# SMD_RGB_COM_BC639_REV5.net
KiCad netlist of a schematic drawn in EAGLE
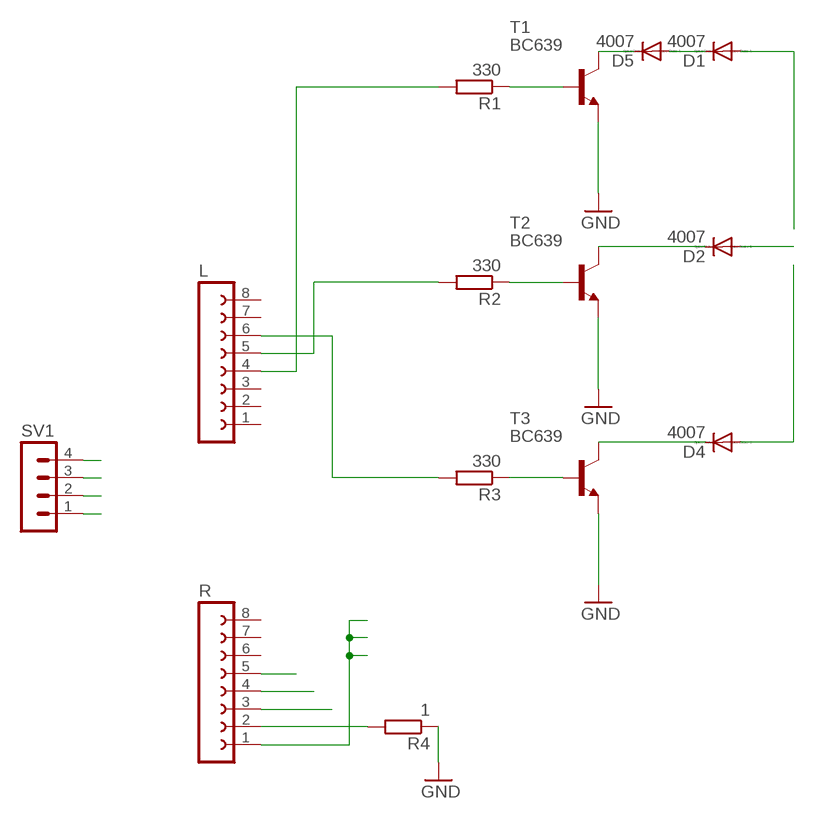
[diagram p0: schematic, sheet 1]

(export (version "E")
  (design (tool "Eeschema 10.0.6"))
  (components
    (comp (ref "D1")
      (value "4007")
      (footprint "eagle-import:DO35-7")
      (libsource (lib "eagle-import") (part "1N4148DO35-7"))
    )
    (comp (ref "D2")
      (value "4007")
      (footprint "eagle-import:DO35-7")
      (libsource (lib "eagle-import") (part "1N4148DO35-7"))
    )
    (comp (ref "D4")
      (value "4007")
      (footprint "eagle-import:DO35-7")
      (libsource (lib "eagle-import") (part "1N4148DO35-7"))
    )
    (comp (ref "D5")
      (value "4007")
      (footprint "eagle-import:DO35-7")
      (libsource (lib "eagle-import") (part "1N4148DO35-7"))
    )
    (comp (ref "L")
      (value "FE08-1")
      (footprint "eagle-import:FE08")
      (libsource (lib "eagle-import") (part "FE08-1"))
    )
    (comp (ref "R")
      (value "FE08-1")
      (footprint "eagle-import:FE08")
      (libsource (lib "eagle-import") (part "FE08-1"))
    )
    (comp (ref "R1")
      (value "330")
      (footprint "eagle-import:0204_7")
      (libsource (lib "eagle-import") (part "R-EU_0204/7"))
    )
    (comp (ref "R2")
      (value "330")
      (footprint "eagle-import:0204_7")
      (libsource (lib "eagle-import") (part "R-EU_0204/7"))
    )
    (comp (ref "R3")
      (value "330")
      (footprint "eagle-import:0204_7")
      (libsource (lib "eagle-import") (part "R-EU_0204/7"))
    )
    (comp (ref "R4")
      (value "1")
      (footprint "eagle-import:0204_7")
      (libsource (lib "eagle-import") (part "R-EU_0204/7"))
    )
    (comp (ref "SV1")
      (value "MA04-1")
      (footprint "eagle-import:MA04-1")
      (libsource (lib "eagle-import") (part "MA04-1"))
    )
    (comp (ref "T1")
      (value "BC639")
      (footprint "eagle-import:TO92-ECB")
      (libsource (lib "eagle-import") (part "-NPN-TO92-ECBBC639"))
    )
    (comp (ref "T2")
      (value "BC639")
      (footprint "eagle-import:TO92-ECB")
      (libsource (lib "eagle-import") (part "-NPN-TO92-ECBBC639"))
    )
    (comp (ref "T3")
      (value "BC639")
      (footprint "eagle-import:TO92-ECB")
      (libsource (lib "eagle-import") (part "-NPN-TO92-ECBBC639"))
    )
  )
  (nets
    (net (code "1") (name "/+5V") (class "Default")
      (node (ref "R") (pin "1") (pinfunction "1_1") (pintype "passive"))
      (node (ref "SV1") (pin "4") (pinfunction "4_4") (pintype "passive"))
    )
    (net (code "2") (name "/BO") (class "Default")
      (node (ref "D4") (pin "A") (pinfunction "A_A") (pintype "passive"))
      (node (ref "SV1") (pin "3") (pinfunction "3_3") (pintype "passive"))
    )
    (net (code "3") (name "/GO") (class "Default")
      (node (ref "D2") (pin "A") (pinfunction "A_A") (pintype "passive"))
      (node (ref "SV1") (pin "2") (pinfunction "2_2") (pintype "passive"))
    )
    (net (code "4") (name "/RO") (class "Default")
      (node (ref "D1") (pin "A") (pinfunction "A_A") (pintype "passive"))
      (node (ref "SV1") (pin "1") (pinfunction "1_1") (pintype "passive"))
    )
    (net (code "5") (name "GND") (class "Default")
      (node (ref "R4") (pin "1") (pinfunction "1_1") (pintype "passive"))
      (node (ref "T1") (pin "E") (pinfunction "E_E") (pintype "passive"))
      (node (ref "T2") (pin "E") (pinfunction "E_E") (pintype "passive"))
      (node (ref "T3") (pin "E") (pinfunction "E_E") (pintype "passive"))
    )
    (net (code "6") (name "Net-(D1-PadC)") (class "Default")
      (node (ref "D1") (pin "C") (pinfunction "C_C") (pintype "passive"))
      (node (ref "D5") (pin "A") (pinfunction "A_A") (pintype "passive"))
    )
    (net (code "7") (name "Net-(D2-PadC)") (class "Default")
      (node (ref "D2") (pin "C") (pinfunction "C_C") (pintype "passive"))
      (node (ref "T2") (pin "C") (pinfunction "C_C") (pintype "passive"))
    )
    (net (code "8") (name "Net-(D4-PadC)") (class "Default")
      (node (ref "D4") (pin "C") (pinfunction "C_C") (pintype "passive"))
      (node (ref "T3") (pin "C") (pinfunction "C_C") (pintype "passive"))
    )
    (net (code "9") (name "Net-(D5-PadC)") (class "Default")
      (node (ref "D5") (pin "C") (pinfunction "C_C") (pintype "passive"))
      (node (ref "T1") (pin "C") (pinfunction "C_C") (pintype "passive"))
    )
    (net (code "10") (name "Net-(L-Pad4)") (class "Default")
      (node (ref "L") (pin "4") (pinfunction "4_4") (pintype "passive"))
      (node (ref "R1") (pin "2") (pinfunction "2_2") (pintype "passive"))
    )
    (net (code "11") (name "Net-(L-Pad5)") (class "Default")
      (node (ref "L") (pin "5") (pinfunction "5_5") (pintype "passive"))
      (node (ref "R2") (pin "2") (pinfunction "2_2") (pintype "passive"))
    )
    (net (code "12") (name "Net-(L-Pad6)") (class "Default")
      (node (ref "L") (pin "6") (pinfunction "6_6") (pintype "passive"))
      (node (ref "R3") (pin "2") (pinfunction "2_2") (pintype "passive"))
    )
    (net (code "13") (name "Net-(R-Pad2)") (class "Default")
      (node (ref "R") (pin "2") (pinfunction "2_2") (pintype "passive"))
      (node (ref "R4") (pin "2") (pinfunction "2_2") (pintype "passive"))
    )
    (net (code "14") (name "Net-(R1-Pad1)") (class "Default")
      (node (ref "R1") (pin "1") (pinfunction "1_1") (pintype "passive"))
      (node (ref "T1") (pin "B") (pinfunction "B_B") (pintype "passive"))
    )
    (net (code "15") (name "Net-(R2-Pad1)") (class "Default")
      (node (ref "R2") (pin "1") (pinfunction "1_1") (pintype "passive"))
      (node (ref "T2") (pin "B") (pinfunction "B_B") (pintype "passive"))
    )
    (net (code "16") (name "Net-(R3-Pad1)") (class "Default")
      (node (ref "R3") (pin "1") (pinfunction "1_1") (pintype "passive"))
      (node (ref "T3") (pin "B") (pinfunction "B_B") (pintype "passive"))
    )
    (net (code "17") (name "unconnected-(L-Pad1)") (class "Default")
      (node (ref "L") (pin "1") (pinfunction "1_1") (pintype "passive"))
    )
    (net (code "18") (name "unconnected-(L-Pad2)") (class "Default")
      (node (ref "L") (pin "2") (pinfunction "2_2") (pintype "passive"))
    )
    (net (code "19") (name "unconnected-(L-Pad3)") (class "Default")
      (node (ref "L") (pin "3") (pinfunction "3_3") (pintype "passive"))
    )
    (net (code "20") (name "unconnected-(L-Pad7)") (class "Default")
      (node (ref "L") (pin "7") (pinfunction "7_7") (pintype "passive"))
    )
    (net (code "21") (name "unconnected-(L-Pad8)") (class "Default")
      (node (ref "L") (pin "8") (pinfunction "8_8") (pintype "passive"))
    )
    (net (code "22") (name "unconnected-(R-Pad3)") (class "Default")
      (node (ref "R") (pin "3") (pinfunction "3_3") (pintype "passive"))
    )
    (net (code "23") (name "unconnected-(R-Pad4)") (class "Default")
      (node (ref "R") (pin "4") (pinfunction "4_4") (pintype "passive"))
    )
    (net (code "24") (name "unconnected-(R-Pad5)") (class "Default")
      (node (ref "R") (pin "5") (pinfunction "5_5") (pintype "passive"))
    )
    (net (code "25") (name "unconnected-(R-Pad6)") (class "Default")
      (node (ref "R") (pin "6") (pinfunction "6_6") (pintype "passive"))
    )
    (net (code "26") (name "unconnected-(R-Pad7)") (class "Default")
      (node (ref "R") (pin "7") (pinfunction "7_7") (pintype "passive"))
    )
    (net (code "27") (name "unconnected-(R-Pad8)") (class "Default")
      (node (ref "R") (pin "8") (pinfunction "8_8") (pintype "passive"))
    )
  )
)
